# mixer.net
KiCad netlist of a schematic drawn in Altium Designer
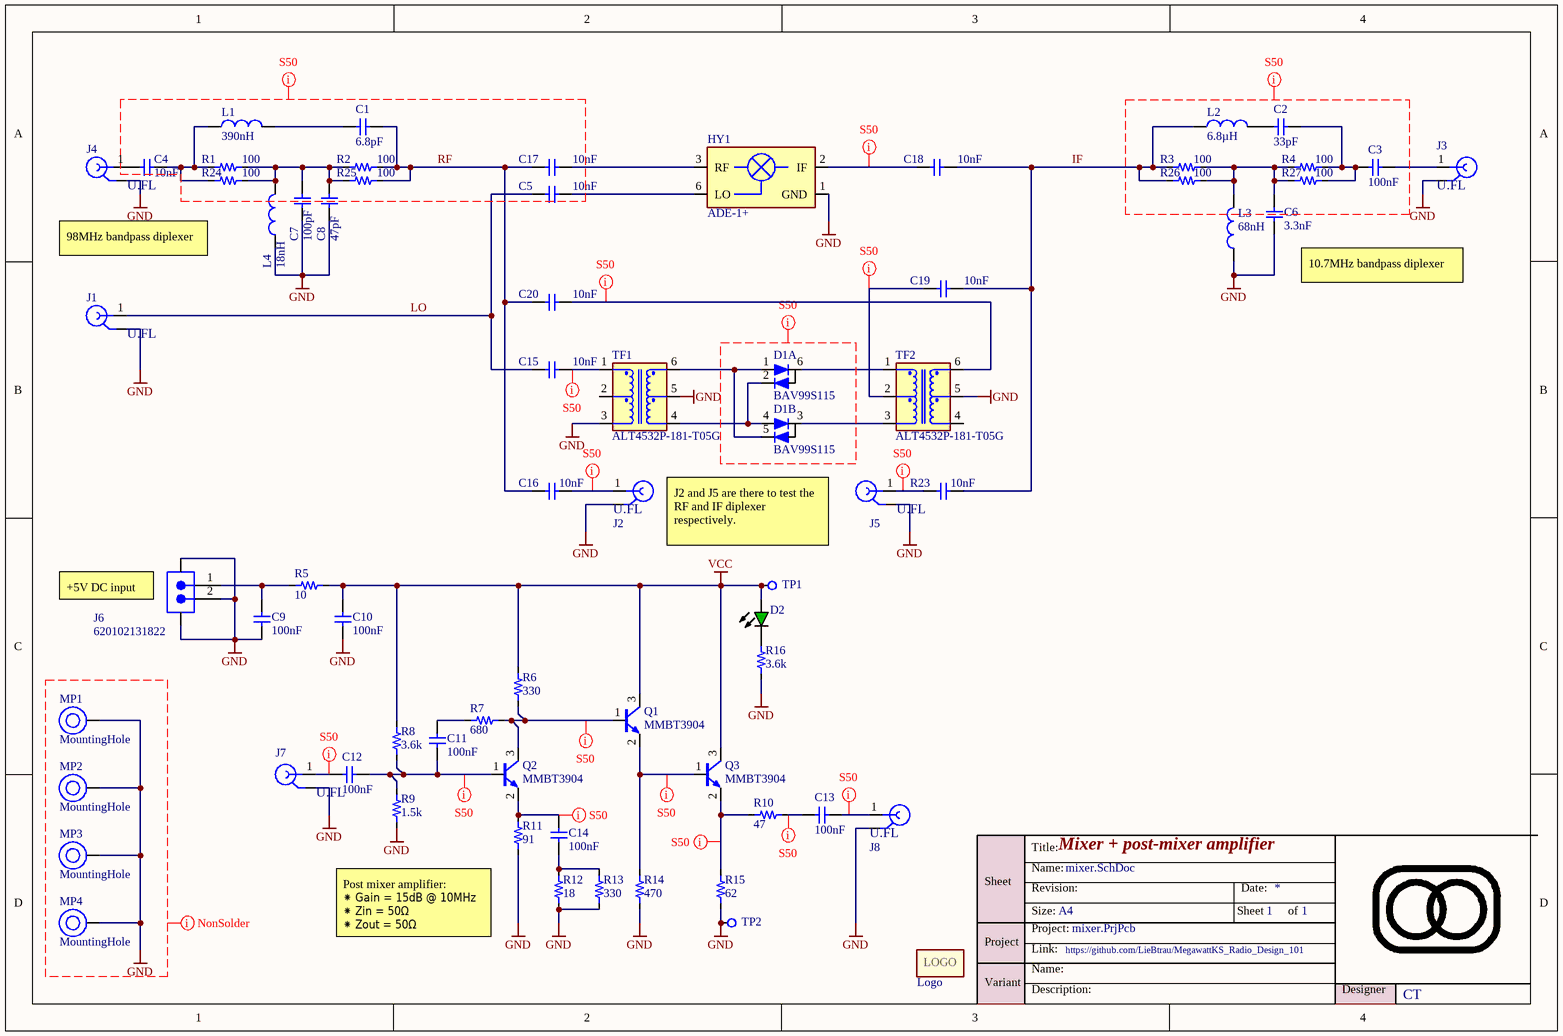
[diagram p0: mixer.SchDoc]

(export (version "E")
  (design (tool "Eeschema 10.0.6"))
  (components
    (comp (ref "C1")
      (value "6.8pF")
      (footprint "0603-C-N")
      (description "WCAP-CSGP Multilayer Ceramic Chip Capacitor, General Purpose, size 0603, NP0, 6.8pF, 50VDC")
      (fields
        (field (name "TOLERANCE") "0.5pF")
        (field (name "Comment") "Capacitor 6.8pF +/-0.5pF 50V NP0 0603")
      )
      (libsource (lib "7c7 Engineering") (part "CAP-NP-2"))
    )
    (comp (ref "C2")
      (value "33pF")
      (footprint "0603-C-N")
      (description "Multilayer Ceramic Capacitor 33 Pf 50 V ½ 1% C0G (NP0) 0603 [1608 Metric]")
      (fields (field (name "JLCPCB PART #") "C519485") (field (name "TOLERANCE") "1%"))
      (libsource (lib "7c7 Engineering") (part "CAP-NP-2"))
    )
    (comp (ref "C3")
      (value "100nF")
      (footprint "0603-C-N")
      (description "Capacitor MLCC, General Purpose, size 0603, X7R, 100nF, +/-10%, 50V")
      (fields (field (name "TOLERANCE") "10%") (field (name "PAGE PART #") "CCQK104"))
      (libsource (lib "7c7 Engineering") (part "CAP-NP-2"))
    )
    (comp (ref "C4")
      (value "10nF")
      (footprint "0603-C-N")
      (description "Multilayer Ceramic Capacitor, Grm Series, 0.01 F, 5%, C0g / Np0, 50 V, 0603 [1608 Metric]")
      (fields (field (name "VOLTAGE") "50V") (field (name "FLIR PART #") "YCAM10N-7"))
      (libsource (lib "7c7 Engineering") (part "CAP-NP-2"))
    )
    (comp (ref "C5")
      (value "10nF")
      (footprint "0603-C-N")
      (description "Multilayer Ceramic Capacitor, Grm Series, 0.01 F, 5%, C0g / Np0, 50 V, 0603 [1608 Metric]")
      (fields (field (name "FLIR PART #") "YCAM10N-7") (field (name "TOLERANCE") "5%"))
      (libsource (lib "7c7 Engineering") (part "CAP-NP-2"))
    )
    (comp (ref "C6")
      (value "3.3nF")
      (footprint "0603-C-N")
      (description "WCAP-CSGP Multilayer Ceramic Chip Capacitor, General Purpose, size 0603, X7R, 3.3nF, 50VDC")
      (fields (field (name "TOLERANCE") "10%") (field (name "Comment") "Capacitor 3.3nF +/-10% 50V X7R 0603"))
      (libsource (lib "7c7 Engineering") (part "CAP-NP-2"))
    )
    (comp (ref "C7")
      (value "100pF")
      (footprint "0603-C-N")
      (description "WCAP-CSGP Multilayer Ceramic Chip Capacitor, General Purpose, size 0603, NP0, 100pF, 50VDC")
      (fields (field (name "TOLERANCE") "5%") (field (name "PAGE PART #") "CCQJ101"))
      (libsource (lib "7c7 Engineering") (part "CAP-NP-2"))
    )
    (comp (ref "C8")
      (value "47pF")
      (footprint "0603-C-N")
      (description "Capacitor MLCC, General Purpose, size 0603, C0G, 47pF, +/-5%, 50V")
      (fields (field (name "TOLERANCE") "5%") (field (name "JLCPCB PART #") "C1671"))
      (libsource (lib "7c7 Engineering") (part "CAP-NP-2"))
    )
    (comp (ref "C9")
      (value "100nF")
      (footprint "0603-C-N")
      (description "Capacitor MLCC, General Purpose, size 0603, X7R, 100nF, +/-10%, 50V")
      (fields (field (name "TOLERANCE") "10%") (field (name "PAGE PART #") "CCQK104"))
      (libsource (lib "7c7 Engineering") (part "CAP-NP-2"))
    )
    (comp (ref "C10")
      (value "100nF")
      (footprint "0603-C-N")
      (description "Capacitor MLCC, General Purpose, size 0603, X7R, 100nF, +/-10%, 50V")
      (fields (field (name "TOLERANCE") "10%") (field (name "PAGE PART #") "CCQK104"))
      (libsource (lib "7c7 Engineering") (part "CAP-NP-2"))
    )
    (comp (ref "C11")
      (value "100nF")
      (footprint "0603-C-N")
      (description "Capacitor MLCC, General Purpose, size 0603, X7R, 100nF, +/-10%, 50V")
      (fields (field (name "TOLERANCE") "10%") (field (name "PAGE PART #") "CCQK104"))
      (libsource (lib "7c7 Engineering") (part "CAP-NP-2"))
    )
    (comp (ref "C12")
      (value "100nF")
      (footprint "0603-C-N")
      (description "Capacitor MLCC, General Purpose, size 0603, X7R, 100nF, +/-10%, 50V")
      (fields (field (name "TOLERANCE") "10%") (field (name "PAGE PART #") "CCQK104"))
      (libsource (lib "7c7 Engineering") (part "CAP-NP-2"))
    )
    (comp (ref "C13")
      (value "100nF")
      (footprint "0603-C-N")
      (description "Capacitor MLCC, General Purpose, size 0603, X7R, 100nF, +/-10%, 50V")
      (fields (field (name "TOLERANCE") "10%") (field (name "PAGE PART #") "CCQK104"))
      (libsource (lib "7c7 Engineering") (part "CAP-NP-2"))
    )
    (comp (ref "C14")
      (value "100nF")
      (footprint "0603-C-N")
      (description "Capacitor MLCC, General Purpose, size 0603, X7R, 100nF, +/-10%, 50V")
      (fields (field (name "TOLERANCE") "10%") (field (name "PAGE PART #") "CCQK104"))
      (libsource (lib "7c7 Engineering") (part "CAP-NP-2"))
    )
    (comp (ref "C15")
      (value "10nF")
      (footprint "0603-C-N")
      (description "Multilayer Ceramic Capacitor, Grm Series, 0.01 F, 5%, C0g / Np0, 50 V, 0603 [1608 Metric]")
      (fields (field (name "FLIR PART #") "YCAM10N-7") (field (name "TOLERANCE") "5%"))
      (libsource (lib "7c7 Engineering") (part "CAP-NP-2"))
    )
    (comp (ref "C16")
      (value "10nF")
      (footprint "0603-C-N")
      (description "Multilayer Ceramic Capacitor, Grm Series, 0.01 F, 5%, C0g / Np0, 50 V, 0603 [1608 Metric]")
      (fields (field (name "FLIR PART #") "YCAM10N-7") (field (name "TOLERANCE") "5%"))
      (libsource (lib "7c7 Engineering") (part "CAP-NP-2"))
    )
    (comp (ref "C17")
      (value "10nF")
      (footprint "0603-C-N")
      (description "Multilayer Ceramic Capacitor, Grm Series, 0.01 F, 5%, C0g / Np0, 50 V, 0603 [1608 Metric]")
      (fields (field (name "FLIR PART #") "YCAM10N-7") (field (name "TOLERANCE") "5%"))
      (libsource (lib "7c7 Engineering") (part "CAP-NP-2"))
    )
    (comp (ref "C18")
      (value "10nF")
      (footprint "0603-C-N")
      (description "Multilayer Ceramic Capacitor, Grm Series, 0.01 F, 5%, C0g / Np0, 50 V, 0603 [1608 Metric]")
      (fields (field (name "FLIR PART #") "YCAM10N-7") (field (name "TOLERANCE") "5%"))
      (libsource (lib "7c7 Engineering") (part "CAP-NP-2"))
    )
    (comp (ref "C19")
      (value "10nF")
      (footprint "0603-C-N")
      (description "Multilayer Ceramic Capacitor, Grm Series, 0.01 F, 5%, C0g / Np0, 50 V, 0603 [1608 Metric]")
      (fields (field (name "FLIR PART #") "YCAM10N-7") (field (name "TOLERANCE") "5%"))
      (libsource (lib "7c7 Engineering") (part "CAP-NP-2"))
    )
    (comp (ref "C20")
      (value "10nF")
      (footprint "0603-C-N")
      (description "Multilayer Ceramic Capacitor, Grm Series, 0.01 F, 5%, C0g / Np0, 50 V, 0603 [1608 Metric]")
      (fields (field (name "FLIR PART #") "YCAM10N-7") (field (name "TOLERANCE") "5%"))
      (libsource (lib "7c7 Engineering") (part "CAP-NP-2"))
    )
    (comp (ref "D1")
      (value "BAV99S115")
      (footprint "SOT-363-N")
      (description "Diode-gp Power Switching")
      (fields (field (name "JLCPCB PART #") "C96225") (field (name "VOLTAGE") "75V"))
      (libsource (lib "7c7 Engineering") (part "BAV99S115"))
    )
    (comp (ref "D2")
      (value "150060GS84000")
      (footprint "WL-SMCW_0603_150060xx8x000")
      (description "WL-SMCW Mono-color Chip LED Waterclear, size 0603, Green, 3.3V, 40°")
      (fields (field (name "JLCPCB PART #") "C7429914") (field (name "MANUFACTURER") "Wurth Elektronik"))
      (libsource (lib "7c7 Engineering") (part "LED-GREEN-2"))
    )
    (comp (ref "GR1")
      (value "Logo")
      (footprint "LOGO_9x6mm")
      (libsource (lib "Integrated_Library_LieBtrau") (part "Logo"))
    )
    (comp (ref "HY1")
      (value "ADE-1+")
      (footprint "ADE-1+")
      (description "Double Balanced Mixer, 0.5MHz Min, 500MHz Max, 7.8dB Conversion Loss-Max")
      (fields (field (name "JLCPCB PART #") "C2942210"))
      (libsource (lib "7c7 Engineering") (part "HY_ADE-1+"))
    )
    (comp (ref "J1")
      (value "U.FL-R-SMT(10)")
      (footprint "HRS-U.FL-R-SMT_V")
      (fields (field (name "JLCPCB PART #") "C88373") (field (name "MANUFACTURER") "Hirose Electric"))
      (libsource (lib "7c7 Engineering") (part "CN_COAX"))
    )
    (comp (ref "J2")
      (value "U.FL-R-SMT(10)")
      (footprint "HRS-U.FL-R-SMT_V")
      (fields (field (name "JLCPCB PART #") "C88373") (field (name "MANUFACTURER") "Hirose Electric"))
      (libsource (lib "") (part "CN_COAX_1"))
    )
    (comp (ref "J3")
      (value "U.FL-R-SMT(10)")
      (footprint "HRS-U.FL-R-SMT_V")
      (fields (field (name "JLCPCB PART #") "C88373") (field (name "MANUFACTURER") "Hirose Electric"))
      (libsource (lib "") (part "CN_COAX_1"))
    )
    (comp (ref "J4")
      (value "U.FL-R-SMT(10)")
      (footprint "HRS-U.FL-R-SMT_V")
      (fields (field (name "JLCPCB PART #") "C88373") (field (name "MANUFACTURER") "Hirose Electric"))
      (libsource (lib "7c7 Engineering") (part "CN_COAX"))
    )
    (comp (ref "J5")
      (value "U.FL-R-SMT(10)")
      (footprint "HRS-U.FL-R-SMT_V")
      (fields (field (name "JLCPCB PART #") "C88373") (field (name "MANUFACTURER") "Hirose Electric"))
      (libsource (lib "7c7 Engineering") (part "CN_COAX"))
    )
    (comp (ref "J6")
      (value "620102131822")
      (footprint "620102131822")
      (description "WR-WTB SMT Male Horizontal Shrouded Header, pitch 2mm, 2p")
      (fields
        (field (name "JLCPCB PART #") "C295747")
        (field (name "PAGE PART #") "K620102131822")
        (field (name "PUBLISHER") "Wurth Elektronik")
      )
      (libsource (lib "7c7 Engineering") (part "HDR_2P_2MP"))
    )
    (comp (ref "J7")
      (value "U.FL-R-SMT(10)")
      (footprint "HRS-U.FL-R-SMT_V")
      (fields (field (name "JLCPCB PART #") "C88373") (field (name "MANUFACTURER") "Hirose Electric"))
      (libsource (lib "7c7 Engineering") (part "CN_COAX"))
    )
    (comp (ref "J8")
      (value "U.FL-R-SMT(10)")
      (footprint "HRS-U.FL-R-SMT_V")
      (fields (field (name "JLCPCB PART #") "C88373") (field (name "MANUFACTURER") "Hirose Electric"))
      (libsource (lib "") (part "CN_COAX_1"))
    )
    (comp (ref "L1")
      (value "744762239GA")
      (footprint "WE-KI_1008")
      (description "WE-KI SMT Wire Wound Ceramic Inductor, size 1008, 390nH, 0.47A")
      (fields (field (name "INDUCTANCE") "390nH") (field (name "MANUFACTURER") "Wurth Elektronik"))
      (libsource (lib "7c7 Engineering") (part "IND"))
    )
    (comp (ref "L2")
      (value "744758368A")
      (footprint "WE-RFH_1008A")
      (description "WE-RFH SMT Ferrite Inductor, size 1008A, 6.8µH, 0.36A, 2O")
      (fields (field (name "MANUFACTURER") "Wurth Elektronik") (field (name "INDUCTANCE") "6.8µH"))
      (libsource (lib "7c7 Engineering") (part "IND"))
    )
    (comp (ref "L3")
      (value "744762168GA")
      (footprint "WE-KI_1008")
      (description "WE-KI SMT Wire Wound Ceramic Inductor, size 1008, 68nH, 1A")
      (fields (field (name "INDUCTANCE") "68nH") (field (name "MANUFACTURER") "Wurth Elektronik"))
      (libsource (lib "7c7 Engineering") (part "IND"))
    )
    (comp (ref "L4")
      (value "744762118A")
      (footprint "WE-KI_1008")
      (description "WE-KI SMT Wire Wound Ceramic Inductor, size 1008, 18nH, 1A")
      (fields (field (name "MANUFACTURER") "Wurth Elektronik") (field (name "INDUCTANCE") "18nH"))
      (libsource (lib "7c7 Engineering") (part "IND"))
    )
    (comp (ref "MP1")
      (value "MountingHole")
      (footprint "PTH-M3D6.5_VIA-RING")
      (libsource (lib "7c7 Engineering") (part "MECH_NO_BOM"))
    )
    (comp (ref "MP2")
      (value "MountingHole")
      (footprint "PTH-M3D6.5_VIA-RING")
      (libsource (lib "7c7 Engineering") (part "MECH_NO_BOM"))
    )
    (comp (ref "MP3")
      (value "MountingHole")
      (footprint "PTH-M3D6.5_VIA-RING")
      (libsource (lib "7c7 Engineering") (part "MECH_NO_BOM"))
    )
    (comp (ref "MP4")
      (value "MountingHole")
      (footprint "PTH-M3D6.5_VIA-RING")
      (libsource (lib "7c7 Engineering") (part "MECH_NO_BOM"))
    )
    (comp (ref "Q1")
      (value "MMBT3904")
      (footprint "SOT-23-3-N")
      (description "NPN General Purpose Amplifier, 40 V, 0.2 A, -55 to 150 degC, 3-Pin SOT23, RoHS, Tape and Reel")
      (fields (field (name "MANUFACTURER") "Fairchild Semiconductor") (field (name "POWER") "625mW"))
      (libsource (lib "7c7 Engineering") (part "BJT-NPN-BEC"))
    )
    (comp (ref "Q2")
      (value "MMBT3904")
      (footprint "SOT-23-3-N")
      (description "NPN General Purpose Amplifier, 40 V, 0.2 A, -55 to 150 degC, 3-Pin SOT23, RoHS, Tape and Reel")
      (fields (field (name "MANUFACTURER") "Fairchild Semiconductor") (field (name "POWER") "625mW"))
      (libsource (lib "7c7 Engineering") (part "BJT-NPN-BEC"))
    )
    (comp (ref "Q3")
      (value "MMBT3904")
      (footprint "SOT-23-3-N")
      (description "NPN General Purpose Amplifier, 40 V, 0.2 A, -55 to 150 degC, 3-Pin SOT23, RoHS, Tape and Reel")
      (fields (field (name "MANUFACTURER") "Fairchild Semiconductor") (field (name "POWER") "625mW"))
      (libsource (lib "7c7 Engineering") (part "BJT-NPN-BEC"))
    )
    (comp (ref "R1")
      (value "100")
      (footprint "0603-R-N")
      (description "Chip Resistor, Thick Film, General Purpose, 0603, 63mW, 50V, 100 Ohm, +/-1%")
      (fields (field (name "JLCPCB PART #") "C22775") (field (name "TOLERANCE") "1%"))
      (libsource (lib "7c7 Engineering") (part "RES"))
    )
    (comp (ref "R2")
      (value "100")
      (footprint "0603-R-N")
      (description "Chip Resistor, Thick Film, General Purpose, 0603, 63mW, 50V, 100 Ohm, +/-1%")
      (fields (field (name "JLCPCB PART #") "C22775") (field (name "TOLERANCE") "1%"))
      (libsource (lib "7c7 Engineering") (part "RES"))
    )
    (comp (ref "R3")
      (value "100")
      (footprint "0603-R-N")
      (description "Chip Resistor, Thick Film, General Purpose, 0603, 63mW, 50V, 100 Ohm, +/-1%")
      (fields (field (name "JLCPCB PART #") "C22775") (field (name "TOLERANCE") "1%"))
      (libsource (lib "7c7 Engineering") (part "RES"))
    )
    (comp (ref "R4")
      (value "100")
      (footprint "0603-R-N")
      (description "Chip Resistor, Thick Film, General Purpose, 0603, 63mW, 50V, 100 Ohm, +/-1%")
      (fields (field (name "JLCPCB PART #") "C22775") (field (name "TOLERANCE") "1%"))
      (libsource (lib "7c7 Engineering") (part "RES"))
    )
    (comp (ref "R5")
      (value "10")
      (footprint "0603-R-N")
      (description "Chip Resistor, Thick Film, General Purpose, 0603, 100mW, 50V, 10 Ohm, +/-1%")
      (fields (field (name "TOLERANCE") "1%") (field (name "JLCPCB PART #") "C22859"))
      (libsource (lib "7c7 Engineering") (part "RES"))
    )
    (comp (ref "R6")
      (value "330")
      (footprint "0603-R-N")
      (description "Chip Resistor, Thick Film, General Purpose, 0603, 100mW, 50V, 330 Ohm, +/-1%")
      (fields (field (name "JLCPCB PART #") "C23138") (field (name "TOLERANCE") "1%"))
      (libsource (lib "7c7 Engineering") (part "RES"))
    )
    (comp (ref "R7")
      (value "680")
      (footprint "0603-R-N")
      (description "SMD Chip Resistor, 680 Ohm, ï¿½ 1%, 100 mW, 0603 [1608 Metric], Thick Film, Precision")
      (fields (field (name "TOLERANCE") "1%") (field (name "JLCPCB PART #") "C23228"))
      (libsource (lib "7c7 Engineering") (part "RES"))
    )
    (comp (ref "R8")
      (value "3.6k")
      (footprint "0603-R-N")
      (description "Res Thick Film 0603 3.6K Ohm 1% 0.1W(1/10W) ±100ppm/°C Pad SMD T/R")
      (fields
        (field (name "JLCPCB PART #") "C22980")
        (field (name "Comment") "Resistor 3.6k +/-0.1W 1% 0603")
      )
      (libsource (lib "7c7 Engineering") (part "RES"))
    )
    (comp (ref "R9")
      (value "1.5k")
      (footprint "0603-R-N")
      (description "Chip Resistor, Thick Film, General Purpose, 0603, 100mW, 50V, 1.5 kOhm, +/-1%")
      (fields (field (name "TOLERANCE") "1%") (field (name "JLCPCB PART #") "C22843"))
      (libsource (lib "7c7 Engineering") (part "RES"))
    )
    (comp (ref "R10")
      (value "47")
      (footprint "0603-R-N")
      (description "SMD Chip Resistor, 47 Ohm, ± 1%, 100 mW, 0603 [1608 Metric], Thick Film, General Purpose")
      (fields (field (name "JLCPCB PART #") "C23182") (field (name "TOLERANCE") "1%"))
      (libsource (lib "7c7 Engineering") (part "RES"))
    )
    (comp (ref "R11")
      (value "91")
      (footprint "0603-R-N")
      (description "SMD Chip Resistor, 91 Ohm, ± 1%, 100 mW, 0603 [1608 Metric], Thick Film, General Purpose")
      (fields (field (name "TOLERANCE") "1%") (field (name "JLCPCB PART #") "C2960792"))
      (libsource (lib "7c7 Engineering") (part "RES"))
    )
    (comp (ref "R12")
      (value "18")
      (footprint "0603-R-N")
      (description "SMD Chip Resistor, 18 ohm, ï¿½ 1%, 100 mW, 0603 [1608 Metric], Thick Film, General Purpose")
      (fields (field (name "TOLERANCE") "1%") (field (name "JLCPCB PART #") "C2933165"))
      (libsource (lib "7c7 Engineering") (part "RES"))
    )
    (comp (ref "R13")
      (value "330")
      (footprint "0603-R-N")
      (description "Chip Resistor, Thick Film, General Purpose, 0603, 100mW, 50V, 330 Ohm, +/-1%")
      (fields (field (name "JLCPCB PART #") "C23138") (field (name "TOLERANCE") "1%"))
      (libsource (lib "7c7 Engineering") (part "RES"))
    )
    (comp (ref "R14")
      (value "470")
      (footprint "0603-R-N")
      (description "Chip Resistor, Thick Film, General Purpose, 0603, 100mW, 50V, 470 Ohm, +/-1%")
      (fields (field (name "JLCPCB PART #") "C23179") (field (name "TOLERANCE") "1%"))
      (libsource (lib "7c7 Engineering") (part "RES"))
    )
    (comp (ref "R15")
      (value "62")
      (footprint "0603-R-N")
      (description "Res Thick Film 0603 62 Ohm 1% 1/10W ±100ppm/°C Molded SMD SMD Paper T/R")
      (fields (field (name "JLCPCB PART #") "C23222") (field (name "TOLERANCE") "1%"))
      (libsource (lib "7c7 Engineering") (part "RES"))
    )
    (comp (ref "R16")
      (value "3.6k")
      (footprint "0603-R-N")
      (description "Res Thick Film 0603 3.6K Ohm 1% 0.1W(1/10W) ±100ppm/°C Pad SMD T/R")
      (fields
        (field (name "JLCPCB PART #") "C22980")
        (field (name "Comment") "Resistor 3.6k +/-0.1W 1% 0603")
      )
      (libsource (lib "7c7 Engineering") (part "RES"))
    )
    (comp (ref "R23")
      (value "10nF")
      (footprint "0603-C-N")
      (description "Multilayer Ceramic Capacitor, Grm Series, 0.01 F, 5%, C0g / Np0, 50 V, 0603 [1608 Metric]")
      (fields (field (name "FLIR PART #") "YCAM10N-7") (field (name "TOLERANCE") "5%"))
      (libsource (lib "7c7 Engineering") (part "CAP-NP-2"))
    )
    (comp (ref "R24")
      (value "100")
      (footprint "0603-R-N")
      (description "Chip Resistor, Thick Film, General Purpose, 0603, 63mW, 50V, 100 Ohm, +/-1%")
      (fields (field (name "JLCPCB PART #") "C22775") (field (name "TOLERANCE") "1%"))
      (libsource (lib "7c7 Engineering") (part "RES"))
    )
    (comp (ref "R25")
      (value "100")
      (footprint "0603-R-N")
      (description "Chip Resistor, Thick Film, General Purpose, 0603, 63mW, 50V, 100 Ohm, +/-1%")
      (fields (field (name "JLCPCB PART #") "C22775") (field (name "TOLERANCE") "1%"))
      (libsource (lib "7c7 Engineering") (part "RES"))
    )
    (comp (ref "R26")
      (value "100")
      (footprint "0603-R-N")
      (description "Chip Resistor, Thick Film, General Purpose, 0603, 63mW, 50V, 100 Ohm, +/-1%")
      (fields (field (name "JLCPCB PART #") "C22775") (field (name "TOLERANCE") "1%"))
      (libsource (lib "7c7 Engineering") (part "RES"))
    )
    (comp (ref "R27")
      (value "100")
      (footprint "0603-R-N")
      (description "Chip Resistor, Thick Film, General Purpose, 0603, 63mW, 50V, 100 Ohm, +/-1%")
      (fields (field (name "JLCPCB PART #") "C22775") (field (name "TOLERANCE") "1%"))
      (libsource (lib "7c7 Engineering") (part "RES"))
    )
    (comp (ref "TF1")
      (value "ALT4532P-181-T05G")
      (footprint "TF_STD_LAN1000_4532_6P")
      (description "Pulse Transformers and Modules for LAN, Transformer, LxWxH=4.5x3.2x2.9mm")
      (fields (field (name "FLIR PART #") "YTFM1000") (field (name "JLCPCB PART #") "C7501942"))
      (libsource (lib "7c7 Engineering") (part "TF_3P3P"))
    )
    (comp (ref "TF2")
      (value "ALT4532P-181-T05G")
      (footprint "TF_STD_LAN1000_4532_6P")
      (description "Pulse Transformers and Modules for LAN, Transformer, LxWxH=4.5x3.2x2.9mm")
      (fields (field (name "FLIR PART #") "YTFM1000") (field (name "JLCPCB PART #") "C7501942"))
      (libsource (lib "7c7 Engineering") (part "TF_3P3P"))
    )
    (comp (ref "TP1")
      (value "Testpad with multiple sizes")
      (footprint "TP_1.5mm_0.3mmHole")
      (description "Testpad land")
      (libsource (lib "7c7 Engineering") (part "Testpad"))
    )
    (comp (ref "TP2")
      (value "Testpad with multiple sizes")
      (footprint "TP_1.5mm_0.3mmHole")
      (description "Testpad land")
      (libsource (lib "7c7 Engineering") (part "Testpad"))
    )
  )
  (nets
    (net (code "1") (name "/IF") (class "Default")
      (node (ref "C18") (pin "2") (pinfunction "2_2") (pintype "passive"))
      (node (ref "C19") (pin "2") (pinfunction "2_2") (pintype "passive"))
      (node (ref "L2") (pin "1") (pinfunction "1_1") (pintype "passive"))
      (node (ref "R23") (pin "2") (pinfunction "2_2") (pintype "passive"))
      (node (ref "R26") (pin "1") (pinfunction "1_1") (pintype "passive"))
      (node (ref "R3") (pin "1") (pinfunction "1_1") (pintype "passive"))
    )
    (net (code "2") (name "/LO") (class "Default")
      (node (ref "C15") (pin "1") (pinfunction "1_1") (pintype "passive"))
      (node (ref "C5") (pin "1") (pinfunction "1_1") (pintype "passive"))
      (node (ref "J1") (pin "1") (pinfunction "SIG_1") (pintype "passive"))
    )
    (net (code "3") (name "/RF") (class "Default")
      (node (ref "C1") (pin "2") (pinfunction "2_2") (pintype "passive"))
      (node (ref "C16") (pin "1") (pinfunction "1_1") (pintype "passive"))
      (node (ref "C17") (pin "1") (pinfunction "1_1") (pintype "passive"))
      (node (ref "C20") (pin "1") (pinfunction "1_1") (pintype "passive"))
      (node (ref "R2") (pin "2") (pinfunction "2_2") (pintype "passive"))
      (node (ref "R25") (pin "2") (pinfunction "2_2") (pintype "passive"))
    )
    (net (code "4") (name "GND") (class "Default")
      (node (ref "C10") (pin "1") (pinfunction "1_1") (pintype "passive"))
      (node (ref "C6") (pin "1") (pinfunction "1_1") (pintype "passive"))
      (node (ref "C7") (pin "1") (pinfunction "1_1") (pintype "passive"))
      (node (ref "C8") (pin "1") (pinfunction "1_1") (pintype "passive"))
      (node (ref "C9") (pin "1") (pinfunction "1_1") (pintype "passive"))
      (node (ref "HY1") (pin "1") (pinfunction "GND_1") (pintype "passive"))
      (node (ref "J1") (pin "2") (pinfunction "GND_2") (pintype "passive"))
      (node (ref "J2") (pin "2") (pinfunction "GND_2") (pintype "passive"))
      (node (ref "J3") (pin "2") (pinfunction "GND_2") (pintype "passive"))
      (node (ref "J4") (pin "2") (pinfunction "GND_2") (pintype "passive"))
      (node (ref "J5") (pin "2") (pinfunction "GND_2") (pintype "passive"))
      (node (ref "J6") (pin "2") (pinfunction "2_2") (pintype "passive"))
      (node (ref "J6") (pin "MP1") (pinfunction "MP1_MP1") (pintype "passive"))
      (node (ref "J6") (pin "MP2") (pinfunction "MP2_MP2") (pintype "passive"))
      (node (ref "J7") (pin "2") (pinfunction "GND_2") (pintype "passive"))
      (node (ref "J8") (pin "2") (pinfunction "GND_2") (pintype "passive"))
      (node (ref "L3") (pin "1") (pinfunction "1_1") (pintype "passive"))
      (node (ref "L4") (pin "1") (pinfunction "1_1") (pintype "passive"))
      (node (ref "MP1") (pin "1") (pinfunction "H1_1") (pintype "passive"))
      (node (ref "MP2") (pin "1") (pinfunction "H1_1") (pintype "passive"))
      (node (ref "MP3") (pin "1") (pinfunction "H1_1") (pintype "passive"))
      (node (ref "MP4") (pin "1") (pinfunction "H1_1") (pintype "passive"))
      (node (ref "R11") (pin "1") (pinfunction "1_1") (pintype "passive"))
      (node (ref "R12") (pin "1") (pinfunction "1_1") (pintype "passive"))
      (node (ref "R13") (pin "1") (pinfunction "1_1") (pintype "passive"))
      (node (ref "R14") (pin "1") (pinfunction "1_1") (pintype "passive"))
      (node (ref "R15") (pin "1") (pinfunction "1_1") (pintype "passive"))
      (node (ref "R16") (pin "1") (pinfunction "1_1") (pintype "passive"))
      (node (ref "R9") (pin "1") (pinfunction "1_1") (pintype "passive"))
      (node (ref "TF1") (pin "3") (pinfunction "Sec1+_3") (pintype "passive"))
      (node (ref "TF1") (pin "5") (pinfunction "Sec1-_5") (pintype "passive"))
      (node (ref "TF2") (pin "5") (pinfunction "Sec1-_5") (pintype "passive"))
      (node (ref "TP2") (pin "1") (pinfunction "Pad_1") (pintype "passive"))
    )
    (net (code "5") (name "Net-(C1-Pad1)") (class "Default")
      (node (ref "C1") (pin "1") (pinfunction "1_1") (pintype "passive"))
      (node (ref "L1") (pin "2") (pinfunction "2_2") (pintype "passive"))
    )
    (net (code "6") (name "Net-(C2-Pad1)") (class "Default")
      (node (ref "C2") (pin "1") (pinfunction "1_1") (pintype "passive"))
      (node (ref "L2") (pin "2") (pinfunction "2_2") (pintype "passive"))
    )
    (net (code "7") (name "Net-(C2-Pad2)") (class "Default")
      (node (ref "C2") (pin "2") (pinfunction "2_2") (pintype "passive"))
      (node (ref "C3") (pin "2") (pinfunction "2_2") (pintype "passive"))
      (node (ref "R27") (pin "2") (pinfunction "2_2") (pintype "passive"))
      (node (ref "R4") (pin "2") (pinfunction "2_2") (pintype "passive"))
    )
    (net (code "8") (name "Net-(C4-Pad2)") (class "Default")
      (node (ref "C4") (pin "2") (pinfunction "2_2") (pintype "passive"))
      (node (ref "L1") (pin "1") (pinfunction "1_1") (pintype "passive"))
      (node (ref "R1") (pin "1") (pinfunction "1_1") (pintype "passive"))
      (node (ref "R24") (pin "1") (pinfunction "1_1") (pintype "passive"))
    )
    (net (code "9") (name "Net-(C6-Pad2)") (class "Default")
      (node (ref "C6") (pin "2") (pinfunction "2_2") (pintype "passive"))
      (node (ref "L3") (pin "2") (pinfunction "2_2") (pintype "passive"))
      (node (ref "R26") (pin "2") (pinfunction "2_2") (pintype "passive"))
      (node (ref "R27") (pin "1") (pinfunction "1_1") (pintype "passive"))
      (node (ref "R3") (pin "2") (pinfunction "2_2") (pintype "passive"))
      (node (ref "R4") (pin "1") (pinfunction "1_1") (pintype "passive"))
    )
    (net (code "10") (name "Net-(C7-Pad2)") (class "Default")
      (node (ref "C7") (pin "2") (pinfunction "2_2") (pintype "passive"))
      (node (ref "C8") (pin "2") (pinfunction "2_2") (pintype "passive"))
      (node (ref "L4") (pin "2") (pinfunction "2_2") (pintype "passive"))
      (node (ref "R1") (pin "2") (pinfunction "2_2") (pintype "passive"))
      (node (ref "R2") (pin "1") (pinfunction "1_1") (pintype "passive"))
      (node (ref "R24") (pin "2") (pinfunction "2_2") (pintype "passive"))
      (node (ref "R25") (pin "1") (pinfunction "1_1") (pintype "passive"))
    )
    (net (code "11") (name "Net-(C9-Pad2)") (class "Default")
      (node (ref "C9") (pin "2") (pinfunction "2_2") (pintype "passive"))
      (node (ref "J6") (pin "1") (pinfunction "1_1") (pintype "passive"))
      (node (ref "R5") (pin "1") (pinfunction "1_1") (pintype "passive"))
    )
    (net (code "12") (name "Net-(C11-Pad1)") (class "Default")
      (node (ref "C11") (pin "1") (pinfunction "1_1") (pintype "passive"))
      (node (ref "R7") (pin "1") (pinfunction "1_1") (pintype "passive"))
    )
    (net (code "13") (name "Net-(C13-Pad1)") (class "Default")
      (node (ref "C13") (pin "1") (pinfunction "1_1") (pintype "passive"))
      (node (ref "R10") (pin "2") (pinfunction "2_2") (pintype "passive"))
    )
    (net (code "14") (name "Net-(C14-Pad2)") (class "Default")
      (node (ref "C14") (pin "2") (pinfunction "2_2") (pintype "passive"))
      (node (ref "R12") (pin "2") (pinfunction "2_2") (pintype "passive"))
      (node (ref "R13") (pin "2") (pinfunction "2_2") (pintype "passive"))
    )
    (net (code "15") (name "Net-(D1A-A)") (class "Default")
      (node (ref "D1") (pin "1") (pinfunction "A_1") (pintype "passive"))
      (node (ref "D1") (pin "5") (pinfunction "C_5") (pintype "passive"))
      (node (ref "TF1") (pin "6") (pinfunction "Pri1-_6") (pintype "passive"))
    )
    (net (code "16") (name "Net-(D1A-C)") (class "Default")
      (node (ref "D1") (pin "2") (pinfunction "C_2") (pintype "passive"))
      (node (ref "D1") (pin "4") (pinfunction "A_4") (pintype "passive"))
      (node (ref "TF1") (pin "4") (pinfunction "Pri2-_4") (pintype "passive"))
    )
    (net (code "17") (name "Net-(D1A-CA)") (class "Default")
      (node (ref "D1") (pin "6") (pinfunction "CA_6") (pintype "passive"))
      (node (ref "TF2") (pin "1") (pinfunction "Pri1+_1") (pintype "passive"))
    )
    (net (code "18") (name "Net-(D1B-CA)") (class "Default")
      (node (ref "D1") (pin "3") (pinfunction "CA_3") (pintype "passive"))
      (node (ref "TF2") (pin "3") (pinfunction "Sec1+_3") (pintype "passive"))
    )
    (net (code "19") (name "Net-(D2-K)") (class "Default")
      (node (ref "D2") (pin "1") (pinfunction "K_1") (pintype "passive"))
      (node (ref "R16") (pin "2") (pinfunction "2_2") (pintype "passive"))
    )
    (net (code "20") (name "Net-(HY1-IF)") (class "Default")
      (node (ref "C18") (pin "1") (pinfunction "1_1") (pintype "passive"))
      (node (ref "HY1") (pin "2") (pinfunction "IF_2") (pintype "passive"))
    )
    (net (code "21") (name "Net-(HY1-LO)") (class "Default")
      (node (ref "C5") (pin "2") (pinfunction "2_2") (pintype "passive"))
      (node (ref "HY1") (pin "6") (pinfunction "LO_6") (pintype "passive"))
    )
    (net (code "22") (name "Net-(HY1-RF)") (class "Default")
      (node (ref "C17") (pin "2") (pinfunction "2_2") (pintype "passive"))
      (node (ref "HY1") (pin "3") (pinfunction "RF_3") (pintype "passive"))
    )
    (net (code "23") (name "Net-(J2-SIG)") (class "Default")
      (node (ref "C16") (pin "2") (pinfunction "2_2") (pintype "passive"))
      (node (ref "J2") (pin "1") (pinfunction "SIG_1") (pintype "passive"))
    )
    (net (code "24") (name "Net-(J3-SIG)") (class "Default")
      (node (ref "C3") (pin "1") (pinfunction "1_1") (pintype "passive"))
      (node (ref "J3") (pin "1") (pinfunction "SIG_1") (pintype "passive"))
    )
    (net (code "25") (name "Net-(J4-SIG)") (class "Default")
      (node (ref "C4") (pin "1") (pinfunction "1_1") (pintype "passive"))
      (node (ref "J4") (pin "1") (pinfunction "SIG_1") (pintype "passive"))
    )
    (net (code "26") (name "Net-(J5-SIG)") (class "Default")
      (node (ref "J5") (pin "1") (pinfunction "SIG_1") (pintype "passive"))
      (node (ref "R23") (pin "1") (pinfunction "1_1") (pintype "passive"))
    )
    (net (code "27") (name "Net-(J7-SIG)") (class "Default")
      (node (ref "C12") (pin "2") (pinfunction "2_2") (pintype "passive"))
      (node (ref "J7") (pin "1") (pinfunction "SIG_1") (pintype "passive"))
    )
    (net (code "28") (name "Net-(J8-SIG)") (class "Default")
      (node (ref "C13") (pin "2") (pinfunction "2_2") (pintype "passive"))
      (node (ref "J8") (pin "1") (pinfunction "SIG_1") (pintype "passive"))
    )
    (net (code "29") (name "Net-(Q1-B)") (class "Default")
      (node (ref "Q1") (pin "1") (pinfunction "B_1") (pintype "passive"))
      (node (ref "Q2") (pin "3") (pinfunction "C_3") (pintype "passive"))
      (node (ref "R6") (pin "1") (pinfunction "1_1") (pintype "passive"))
      (node (ref "R7") (pin "2") (pinfunction "2_2") (pintype "passive"))
    )
    (net (code "30") (name "Net-(Q1-E)") (class "Default")
      (node (ref "Q1") (pin "2") (pinfunction "E_2") (pintype "passive"))
      (node (ref "Q3") (pin "1") (pinfunction "B_1") (pintype "passive"))
      (node (ref "R14") (pin "2") (pinfunction "2_2") (pintype "passive"))
    )
    (net (code "31") (name "Net-(Q2-B)") (class "Default")
      (node (ref "C11") (pin "2") (pinfunction "2_2") (pintype "passive"))
      (node (ref "C12") (pin "1") (pinfunction "1_1") (pintype "passive"))
      (node (ref "Q2") (pin "1") (pinfunction "B_1") (pintype "passive"))
      (node (ref "R8") (pin "1") (pinfunction "1_1") (pintype "passive"))
      (node (ref "R9") (pin "2") (pinfunction "2_2") (pintype "passive"))
    )
    (net (code "32") (name "Net-(Q2-E)") (class "Default")
      (node (ref "C14") (pin "1") (pinfunction "1_1") (pintype "passive"))
      (node (ref "Q2") (pin "2") (pinfunction "E_2") (pintype "passive"))
      (node (ref "R11") (pin "2") (pinfunction "2_2") (pintype "passive"))
    )
    (net (code "33") (name "Net-(Q3-E)") (class "Default")
      (node (ref "Q3") (pin "2") (pinfunction "E_2") (pintype "passive"))
      (node (ref "R10") (pin "1") (pinfunction "1_1") (pintype "passive"))
      (node (ref "R15") (pin "2") (pinfunction "2_2") (pintype "passive"))
    )
    (net (code "34") (name "Net-(TF1-Pri1+)") (class "Default")
      (node (ref "C15") (pin "2") (pinfunction "2_2") (pintype "passive"))
      (node (ref "TF1") (pin "1") (pinfunction "Pri1+_1") (pintype "passive"))
    )
    (net (code "35") (name "Net-(TF2-Pri1-)") (class "Default")
      (node (ref "C20") (pin "2") (pinfunction "2_2") (pintype "passive"))
      (node (ref "TF2") (pin "6") (pinfunction "Pri1-_6") (pintype "passive"))
    )
    (net (code "36") (name "Net-(TF2-Pri2+)") (class "Default")
      (node (ref "C19") (pin "1") (pinfunction "1_1") (pintype "passive"))
      (node (ref "TF2") (pin "2") (pinfunction "Pri2+_2") (pintype "passive"))
    )
    (net (code "37") (name "VCC") (class "Default")
      (node (ref "C10") (pin "2") (pinfunction "2_2") (pintype "passive"))
      (node (ref "D2") (pin "2") (pinfunction "A_2") (pintype "passive"))
      (node (ref "Q1") (pin "3") (pinfunction "C_3") (pintype "passive"))
      (node (ref "Q3") (pin "3") (pinfunction "C_3") (pintype "passive"))
      (node (ref "R5") (pin "2") (pinfunction "2_2") (pintype "passive"))
      (node (ref "R6") (pin "2") (pinfunction "2_2") (pintype "passive"))
      (node (ref "R8") (pin "2") (pinfunction "2_2") (pintype "passive"))
      (node (ref "TP1") (pin "1") (pinfunction "Pad_1") (pintype "passive"))
    )
    (net (code "38") (name "unconnected-(TF1-Pri2+-Pad2)") (class "Default")
      (node (ref "TF1") (pin "2") (pinfunction "Pri2+_2") (pintype "passive"))
    )
    (net (code "39") (name "unconnected-(TF2-Pri2--Pad4)") (class "Default")
      (node (ref "TF2") (pin "4") (pinfunction "Pri2-_4") (pintype "passive"))
    )
  )
)
